# 1_Main.net
KiCad netlist of a schematic drawn in Altium Designer
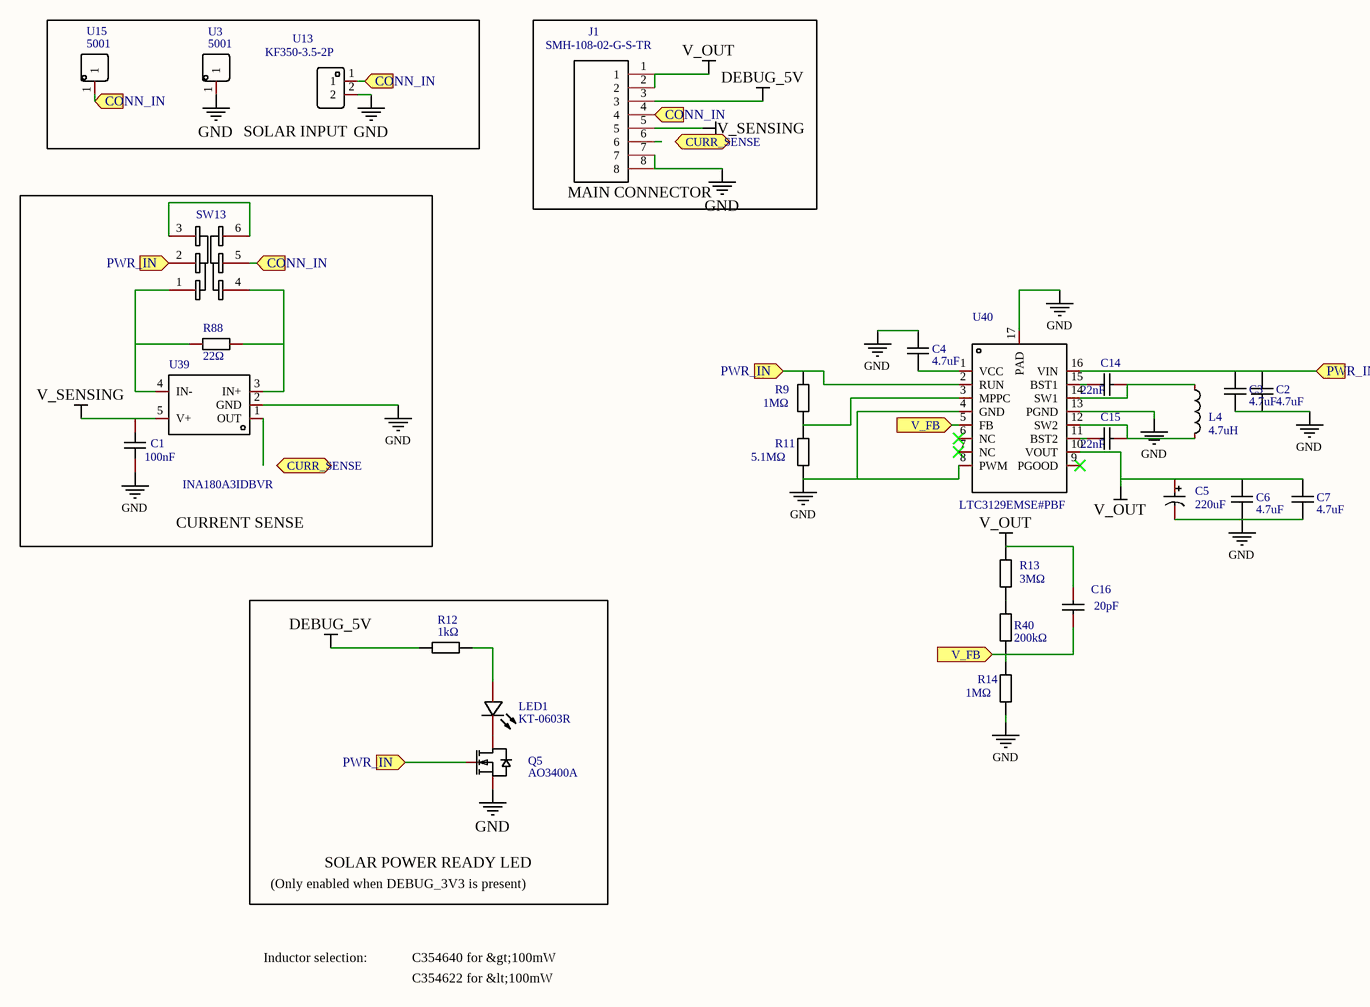
[diagram p0: 1_Main.schdoc]

(export (version "E")
  (design (tool "Eeschema 10.0.6"))
  (components
    (comp (ref "C1")
      (value "100nF")
      (fields
        (field (name "NAME") "100nF")
        (field (name "MANUFACTURER") "YAGEO")
        (field (name "MANUFACTURER PART") "CC0603KRX7R9BB104")
      )
      (libsource (lib "altium-import") (part "root_1_CC0603KRX7R9BB104_"))
    )
    (comp (ref "C2")
      (value "4.7uF")
      (fields
        (field (name "NAME") "4.7uF")
        (field (name "MANUFACTURER PART") "CL10A475KO8NNNC")
        (field (name "MANUFACTURER") "SAMSUNG")
      )
      (libsource (lib "altium-import") (part "root_1_CL10A475KO8NNNC_"))
    )
    (comp (ref "C3")
      (value "4.7uF")
      (fields
        (field (name "NAME") "4.7uF")
        (field (name "MANUFACTURER PART") "CL10A475KO8NNNC")
        (field (name "MANUFACTURER") "SAMSUNG")
      )
      (libsource (lib "altium-import") (part "root_1_CL10A475KO8NNNC_"))
    )
    (comp (ref "C4")
      (value "4.7uF")
      (fields
        (field (name "NAME") "4.7uF")
        (field (name "MANUFACTURER PART") "CL10A475KO8NNNC")
        (field (name "MANUFACTURER") "SAMSUNG")
      )
      (libsource (lib "altium-import") (part "root_1_CL10A475KO8NNNC_"))
    )
    (comp (ref "C5")
      (value "220uF")
      (fields
        (field (name "NAME") "220uF")
        (field (name "MANUFACTURER") "HONOR")
        (field (name "MANUFACTURER PART") "RVT1A221M0605")
      )
      (libsource (lib "altium-import") (part "root_0_RVT1A221M0605_"))
    )
    (comp (ref "C6")
      (value "4.7uF")
      (fields
        (field (name "NAME") "4.7uF")
        (field (name "MANUFACTURER PART") "CL10A475KO8NNNC")
        (field (name "MANUFACTURER") "SAMSUNG")
      )
      (libsource (lib "altium-import") (part "root_1_CL10A475KO8NNNC_"))
    )
    (comp (ref "C7")
      (value "4.7uF")
      (fields
        (field (name "NAME") "4.7uF")
        (field (name "MANUFACTURER PART") "CL10A475KO8NNNC")
        (field (name "MANUFACTURER") "SAMSUNG")
      )
      (libsource (lib "altium-import") (part "root_1_CL10A475KO8NNNC_"))
    )
    (comp (ref "C14")
      (value "22nF")
      (fields
        (field (name "MANUFACTURER") "SAMSUNG(三星)")
        (field (name "MANUFACTURER PART") "CL10B223KB8NNNC")
        (field (name "TOLERANCE") "±10%")
      )
      (libsource (lib "altium-import") (part "root_0_CL10B223KB8NNNC_"))
    )
    (comp (ref "C15")
      (value "22nF")
      (fields
        (field (name "MANUFACTURER") "SAMSUNG(三星)")
        (field (name "MANUFACTURER PART") "CL10B223KB8NNNC")
        (field (name "TOLERANCE") "±10%")
      )
      (libsource (lib "altium-import") (part "root_0_CL10B223KB8NNNC_"))
    )
    (comp (ref "C16")
      (value "20pF")
      (fields
        (field (name "MANUFACTURER") "SAMSUNG(三星)")
        (field (name "MANUFACTURER PART") "CL10C200JB8NNNC")
        (field (name "TOLERANCE") "±5%")
      )
      (libsource (lib "altium-import") (part "root_1_CL10C200JB8NNNC_"))
    )
    (comp (ref "J1")
      (value "SMH-108-02-G-S-TR")
      (fields (field (name "NAME") "SMH-108-02-G-S-TR"))
      (libsource (lib "altium-import") (part "root_0_SMH-108-02-G-S-TR_"))
    )
    (comp (ref "L4")
      (value "4.7uH")
      (fields (field (name "MANUFACTURER") "Sunlord(顺络)") (field (name "MANUFACTURER PART") "SWPA5040S4R7NT"))
      (libsource (lib "altium-import") (part "root_3_SWPA5040S4R7NT_"))
    )
    (comp (ref "LED1")
      (value "KT-0603R")
      (fields (field (name "NAME") "KT-0603R") (field (name "MANUFACTURER") "KENTO"))
      (libsource (lib "altium-import") (part "root_1_KT-0603R_"))
    )
    (comp (ref "Q5")
      (value "AO3400A")
      (fields (field (name "NAME") "AO3400A") (field (name "MANUFACTURER") "AOS"))
      (libsource (lib "altium-import") (part "root_0_AO3400A_"))
    )
    (comp (ref "R9")
      (value "1MΩ")
      (fields
        (field (name "NAME") "1MΩ")
        (field (name "MANUFACTURER") "UniOhm")
        (field (name "MANUFACTURER PART") "0603WAF1004T5E")
      )
      (libsource (lib "altium-import") (part "root_1_0603WAF1004T5E_"))
    )
    (comp (ref "R11")
      (value "5.1MΩ")
      (fields
        (field (name "NAME") "5.1MΩ")
        (field (name "MANUFACTURER") "UniOhm")
        (field (name "MANUFACTURER PART") "0603WAF5104T5E")
      )
      (libsource (lib "altium-import") (part "root_1_0603WAF5104T5E_"))
    )
    (comp (ref "R12")
      (value "1kΩ")
      (fields
        (field (name "NAME") "1kΩ")
        (field (name "MANUFACTURER") "UniOhm")
        (field (name "MANUFACTURER PART") "0603WAF1001T5E")
      )
      (libsource (lib "altium-import") (part "root_0_0603WAF1001T5E_"))
    )
    (comp (ref "R13")
      (value "3MΩ")
      (fields
        (field (name "NAME") "3MΩ")
        (field (name "MANUFACTURER") "UniOhm")
        (field (name "MANUFACTURER PART") "0603WAF3004T5E")
      )
      (libsource (lib "altium-import") (part "root_1_0603WAF3004T5E_"))
    )
    (comp (ref "R14")
      (value "1MΩ")
      (fields
        (field (name "NAME") "1MΩ")
        (field (name "MANUFACTURER") "UniOhm")
        (field (name "MANUFACTURER PART") "0603WAF1004T5E")
      )
      (libsource (lib "altium-import") (part "root_1_0603WAF1004T5E_"))
    )
    (comp (ref "R40")
      (value "200kΩ")
      (fields
        (field (name "NAME") "200kΩ")
        (field (name "MANUFACTURER") "UniOhm")
        (field (name "MANUFACTURER PART") "0603WAF2003T5E")
      )
      (libsource (lib "altium-import") (part "root_3_0603WAF2003T5E_"))
    )
    (comp (ref "R88")
      (value "22Ω")
      (fields
        (field (name "MANUFACTURER") "UNI-ROYAL(厚声)")
        (field (name "MANUFACTURER PART") "0603WAF220JT5E")
        (field (name "TOLERANCE") "±1%")
      )
      (libsource (lib "altium-import") (part "root_0_0603WAF220JT5E_"))
    )
    (comp (ref "SW13")
      (value "K3-2235D-F1")
      (fields (field (name "MANUFACTURER") "韩国韩荣"))
      (libsource (lib "altium-import") (part "root_1_K3-2235D-F1_"))
    )
    (comp (ref "U3")
      (value "5001")
      (fields (field (name "NAME") "5001") (field (name "MANUFACTURER") "Keystone"))
      (libsource (lib "altium-import") (part "root_1_5001_"))
    )
    (comp (ref "U13")
      (value "KF350-3.5-2P")
      (fields (field (name "NAME") "KF350-3.5-2P") (field (name "MANUFACTURER") "Cixi Kefa Elec"))
      (libsource (lib "altium-import") (part "root_2_KF350-3.5-2P_"))
    )
    (comp (ref "U15")
      (value "5001")
      (fields (field (name "NAME") "5001") (field (name "MANUFACTURER") "Keystone"))
      (libsource (lib "altium-import") (part "root_1_5001_"))
    )
    (comp (ref "U39")
      (value "INA180A3IDBVR")
      (fields (field (name "LCSC PART NAME") "INA180A3IDBVR") (field (name "MANUFACTURER") "TI(德州仪器)"))
      (libsource (lib "altium-import") (part "root_2_INA180A3IDBVR_"))
    )
    (comp (ref "U40")
      (value "LTC3129EMSE-1#PBF")
      (fields
        (field (name "LCSC PART NAME") "LTC3129EMSE#PBF")
        (field (name "MANUFACTURER") "ADI(亚德诺)/LINEAR")
        (field (name "MANUFACTURER PART") "LTC3129EMSE#PBF")
      )
      (libsource (lib "altium-import") (part "root_0_LTC3129EMSE-1#PBF_"))
    )
  )
  (nets
    (net (code "1") (name "/CONN_IN") (class "Default")
      (node (ref "J1") (pin "4") (pinfunction "4_4") (pintype "passive"))
      (node (ref "SW13") (pin "5") (pinfunction "5_5") (pintype "passive"))
      (node (ref "U13") (pin "1") (pinfunction "1_1") (pintype "passive"))
      (node (ref "U15") (pin "1") (pinfunction "1_1") (pintype "passive"))
    )
    (net (code "3") (name "/PWR_IN") (class "Default")
      (node (ref "C2") (pin "2") (pinfunction "2_2") (pintype "passive"))
      (node (ref "C3") (pin "2") (pinfunction "2_2") (pintype "passive"))
      (node (ref "Q5") (pin "1") (pinfunction "G_1") (pintype "passive"))
      (node (ref "R9") (pin "2") (pinfunction "2_2") (pintype "passive"))
      (node (ref "SW13") (pin "2") (pinfunction "2_2") (pintype "passive"))
      (node (ref "U40") (pin "16") (pinfunction "VIN_16") (pintype "passive"))
      (node (ref "U40") (pin "2") (pinfunction "RUN_2") (pintype "passive"))
    )
    (net (code "4") (name "/V_FB") (class "Default")
      (node (ref "C16") (pin "1") (pinfunction "1_1") (pintype "passive"))
      (node (ref "R14") (pin "2") (pinfunction "2_2") (pintype "passive"))
      (node (ref "R40") (pin "2") (pinfunction "2_2") (pintype "passive"))
      (node (ref "U40") (pin "5") (pinfunction "FB_5") (pintype "passive"))
    )
    (net (code "5") (name "DEBUG_5V") (class "Default")
      (node (ref "J1") (pin "3") (pinfunction "3_3") (pintype "passive"))
      (node (ref "R12") (pin "1") (pinfunction "1_1") (pintype "passive"))
    )
    (net (code "6") (name "GND") (class "Default")
      (node (ref "C1") (pin "1") (pinfunction "1_1") (pintype "passive"))
      (node (ref "C2") (pin "1") (pinfunction "1_1") (pintype "passive"))
      (node (ref "C3") (pin "1") (pinfunction "1_1") (pintype "passive"))
      (node (ref "C4") (pin "2") (pinfunction "2_2") (pintype "passive"))
      (node (ref "C5") (pin "2") (pinfunction "2_2") (pintype "passive"))
      (node (ref "C6") (pin "1") (pinfunction "1_1") (pintype "passive"))
      (node (ref "C7") (pin "1") (pinfunction "1_1") (pintype "passive"))
      (node (ref "J1") (pin "7") (pinfunction "7_7") (pintype "passive"))
      (node (ref "J1") (pin "8") (pinfunction "8_8") (pintype "passive"))
      (node (ref "Q5") (pin "2") (pinfunction "S_2") (pintype "passive"))
      (node (ref "R11") (pin "2") (pinfunction "2_2") (pintype "passive"))
      (node (ref "R14") (pin "1") (pinfunction "1_1") (pintype "passive"))
      (node (ref "U13") (pin "2") (pinfunction "2_2") (pintype "passive"))
      (node (ref "U3") (pin "1") (pinfunction "1_1") (pintype "passive"))
      (node (ref "U39") (pin "2") (pinfunction "GND_2") (pintype "passive"))
      (node (ref "U40") (pin "13") (pinfunction "PGND_13") (pintype "passive"))
      (node (ref "U40") (pin "17") (pinfunction "PAD_17") (pintype "passive"))
      (node (ref "U40") (pin "4") (pinfunction "GND_4") (pintype "passive"))
      (node (ref "U40") (pin "8") (pinfunction "PWM_8") (pintype "passive"))
    )
    (net (code "7") (name "Net-(LED1-A)") (class "Default")
      (node (ref "LED1") (pin "1") (pinfunction "A_1") (pintype "passive"))
      (node (ref "R12") (pin "2") (pinfunction "2_2") (pintype "passive"))
    )
    (net (code "8") (name "Net-(LED1-K)") (class "Default")
      (node (ref "LED1") (pin "2") (pinfunction "K_2") (pintype "passive"))
      (node (ref "Q5") (pin "3") (pinfunction "D_3") (pintype "passive"))
    )
    (net (code "9") (name "Net-(R13-Pad1)") (class "Default")
      (node (ref "R13") (pin "1") (pinfunction "1_1") (pintype "passive"))
      (node (ref "R40") (pin "1") (pinfunction "1_1") (pintype "passive"))
    )
    (net (code "10") (name "Net-(SW13-Pad3)") (class "Default")
      (node (ref "SW13") (pin "3") (pinfunction "3_3") (pintype "passive"))
      (node (ref "SW13") (pin "6") (pinfunction "6_6") (pintype "passive"))
    )
    (net (code "11") (name "Net-(U39-IN+)") (class "Default")
      (node (ref "R88") (pin "2") (pinfunction "2_2") (pintype "passive"))
      (node (ref "SW13") (pin "4") (pinfunction "4_4") (pintype "passive"))
      (node (ref "U39") (pin "3") (pinfunction "IN+_3") (pintype "passive"))
    )
    (net (code "12") (name "Net-(U39-IN-)") (class "Default")
      (node (ref "R88") (pin "1") (pinfunction "1_1") (pintype "passive"))
      (node (ref "SW13") (pin "1") (pinfunction "1_1") (pintype "passive"))
      (node (ref "U39") (pin "4") (pinfunction "IN-_4") (pintype "passive"))
    )
    (net (code "13") (name "Net-(U40-BST1)") (class "Default")
      (node (ref "C14") (pin "1") (pinfunction "1_1") (pintype "passive"))
      (node (ref "U40") (pin "15") (pinfunction "BST1_15") (pintype "passive"))
    )
    (net (code "14") (name "Net-(U40-BST2)") (class "Default")
      (node (ref "C15") (pin "1") (pinfunction "1_1") (pintype "passive"))
      (node (ref "U40") (pin "11") (pinfunction "BST2_11") (pintype "passive"))
    )
    (net (code "15") (name "Net-(U40-MPPC)") (class "Default")
      (node (ref "R11") (pin "1") (pinfunction "1_1") (pintype "passive"))
      (node (ref "R9") (pin "1") (pinfunction "1_1") (pintype "passive"))
      (node (ref "U40") (pin "3") (pinfunction "MPPC_3") (pintype "passive"))
    )
    (net (code "16") (name "Net-(U40-SW1)") (class "Default")
      (node (ref "C14") (pin "2") (pinfunction "2_2") (pintype "passive"))
      (node (ref "L4") (pin "1") (pinfunction "1_1") (pintype "passive"))
      (node (ref "U40") (pin "14") (pinfunction "SW1_14") (pintype "passive"))
    )
    (net (code "17") (name "Net-(U40-SW2)") (class "Default")
      (node (ref "C15") (pin "2") (pinfunction "2_2") (pintype "passive"))
      (node (ref "L4") (pin "2") (pinfunction "2_2") (pintype "passive"))
      (node (ref "U40") (pin "12") (pinfunction "SW2_12") (pintype "passive"))
    )
    (net (code "18") (name "Net-(U40-VCC)") (class "Default")
      (node (ref "C4") (pin "1") (pinfunction "1_1") (pintype "passive"))
      (node (ref "U40") (pin "1") (pinfunction "VCC_1") (pintype "passive"))
    )
    (net (code "19") (name "V_OUT") (class "Default")
      (node (ref "C16") (pin "2") (pinfunction "2_2") (pintype "passive"))
      (node (ref "C5") (pin "1") (pinfunction "1_1") (pintype "passive"))
      (node (ref "C6") (pin "2") (pinfunction "2_2") (pintype "passive"))
      (node (ref "C7") (pin "2") (pinfunction "2_2") (pintype "passive"))
      (node (ref "J1") (pin "1") (pinfunction "1_1") (pintype "passive"))
      (node (ref "J1") (pin "2") (pinfunction "2_2") (pintype "passive"))
      (node (ref "R13") (pin "2") (pinfunction "2_2") (pintype "passive"))
      (node (ref "U40") (pin "10") (pinfunction "VOUT_10") (pintype "passive"))
    )
    (net (code "20") (name "V_SENSING") (class "Default")
      (node (ref "C1") (pin "2") (pinfunction "2_2") (pintype "passive"))
      (node (ref "J1") (pin "5") (pinfunction "5_5") (pintype "passive"))
      (node (ref "U39") (pin "5") (pinfunction "V+_5") (pintype "passive"))
    )
    (net (code "21") (name "unconnected-(J1-Pad6)") (class "Default")
      (node (ref "J1") (pin "6") (pinfunction "6_6") (pintype "passive"))
    )
    (net (code "22") (name "unconnected-(U39-OUT-Pad1)") (class "Default")
      (node (ref "U39") (pin "1") (pinfunction "OUT_1") (pintype "passive"))
    )
    (net (code "23") (name "unconnected-(U40-NC-Pad6)") (class "Default")
      (node (ref "U40") (pin "6") (pinfunction "NC_6") (pintype "passive+no_connect"))
    )
    (net (code "24") (name "unconnected-(U40-NC-Pad7)") (class "Default")
      (node (ref "U40") (pin "7") (pinfunction "NC_7") (pintype "passive+no_connect"))
    )
    (net (code "25") (name "unconnected-(U40-PGOOD-Pad9)") (class "Default")
      (node (ref "U40") (pin "9") (pinfunction "PGOOD_9") (pintype "passive+no_connect"))
    )
  )
)
